# TS1A.net
KiCad netlist of a schematic drawn in Altium Designer
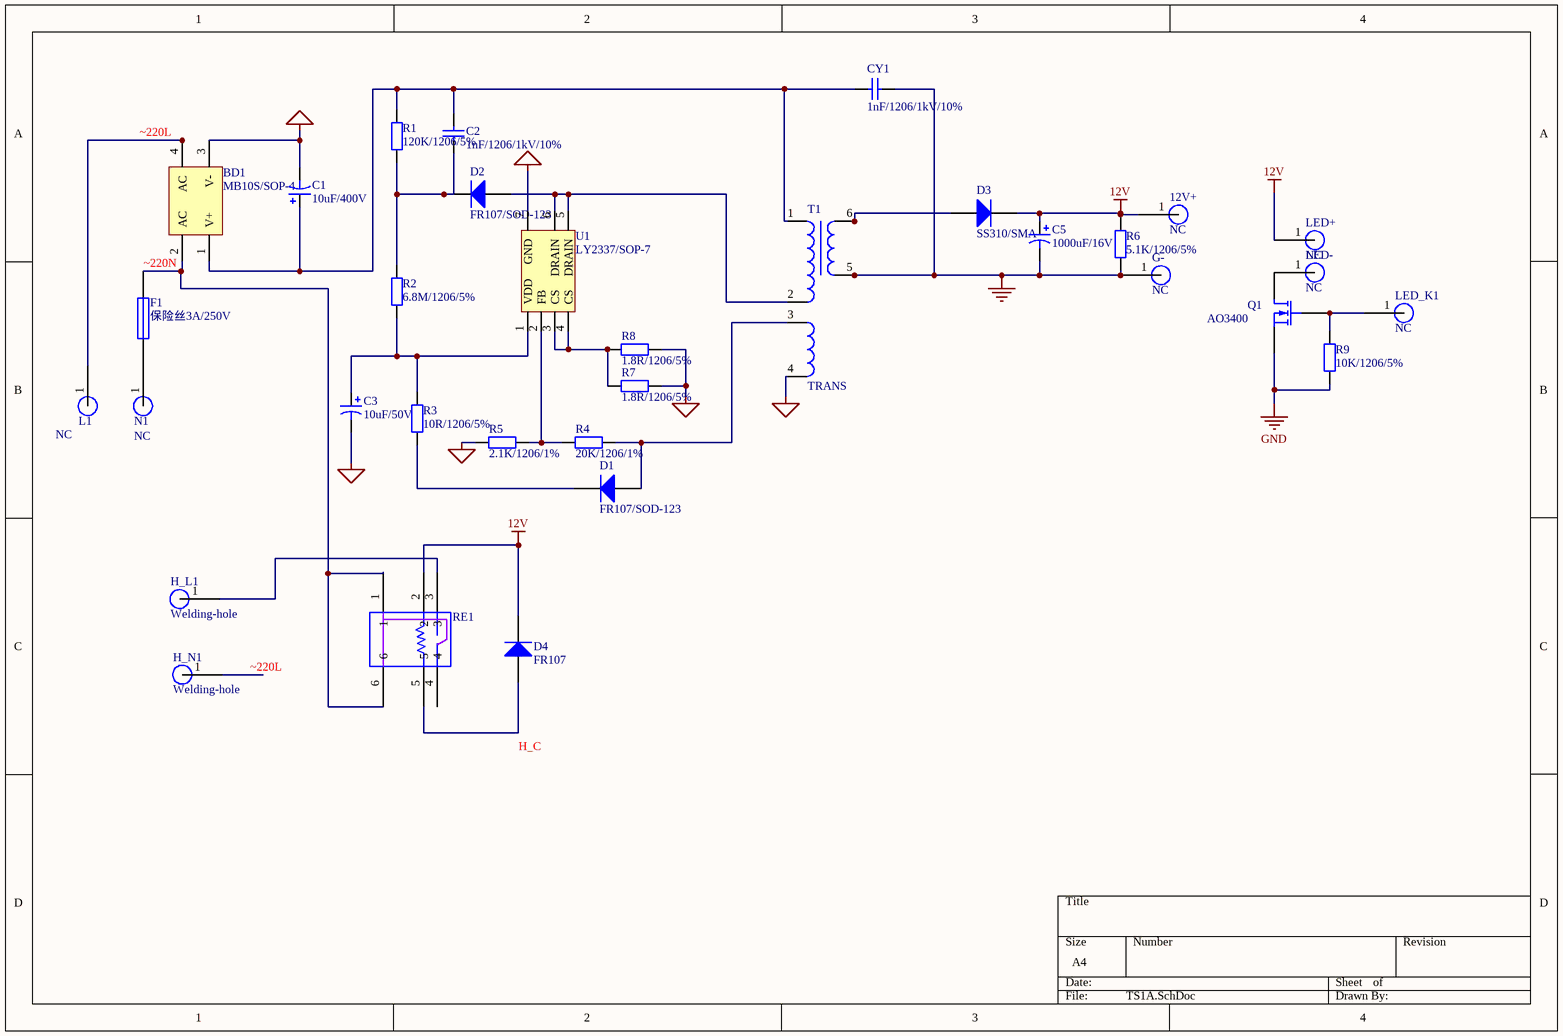
[diagram p0: TS1A.SchDoc]

(export (version "E")
  (design (tool "Eeschema 10.0.6"))
  (components
    (comp (ref "12V+")
      (value "NC")
      (footprint "PAD")
      (description "焊接点")
      (libsource (lib "TS_2A") (part "Welding-hole"))
    )
    (comp (ref "BD1")
      (value "MB10S/SOP-4")
      (footprint "MBL10S")
      (description "整流桥 MB10S/SOP-4")
      (fields (field (name "PUBLISHER") "Altium Limited"))
      (libsource (lib "Miscellaneous Devices") (part "Bridge2"))
    )
    (comp (ref "C1")
      (value "10uF/400V")
      (footprint "400V/10uF 直插电解电容")
      (description "直插电解电容10uF/400V")
      (fields (field (name "PUBLISHER") "Altium Limited"))
      (libsource (lib "Miscellaneous Devices") (part "Cap Pol1"))
    )
    (comp (ref "C2")
      (value "1nF/1206/1kV/10%")
      (footprint "C1206")
      (description "1nF/1206/50V/10%")
      (fields (field (name "PUBLISHER") "Altium Limited"))
      (libsource (lib "Miscellaneous Devices") (part "Cap"))
    )
    (comp (ref "C3")
      (value "10uF/50V")
      (footprint "50V/10uF")
      (description "直插电解电容10uF/50V")
      (fields (field (name "PUBLISHER") "Altium Limited"))
      (libsource (lib "Miscellaneous Devices") (part "Cap Pol1"))
    )
    (comp (ref "C5")
      (value "1000uF/16V")
      (footprint "16V/1000uF")
      (description "直插电解电容1000uF/16V")
      (fields (field (name "PUBLISHER") "Altium Limited"))
      (libsource (lib "Miscellaneous Devices") (part "Cap Pol1"))
    )
    (comp (ref "CY1")
      (value "1nF/1206/1kV/10%")
      (footprint "C1206")
      (description "1nF/1206/50V/10%")
      (fields (field (name "PUBLISHER") "Altium Limited"))
      (libsource (lib "Miscellaneous Devices") (part "Cap"))
    )
    (comp (ref "D1")
      (value "FR107/SOD-123")
      (footprint "SOD123")
      (description "快恢复二极管 FR107 封装SOD-123")
      (fields (field (name "PUBLISHER") "Altium Limited"))
      (libsource (lib "Miscellaneous Devices") (part "Diode"))
    )
    (comp (ref "D2")
      (value "FR107/SOD-123")
      (footprint "SOD123")
      (description "快恢复二极管 FR107 封装SOD-123")
      (fields (field (name "PUBLISHER") "Altium Limited"))
      (libsource (lib "Miscellaneous Devices") (part "Diode"))
    )
    (comp (ref "D3")
      (value "SS310/SMA")
      (footprint "SMA")
      (description "肖特基二极管 SS310/封装 SMA")
      (fields (field (name "PUBLISHER") "Altium Limited"))
      (libsource (lib "Miscellaneous Devices") (part "Diode"))
    )
    (comp (ref "D4")
      (value "FR107")
      (footprint "SOD123")
      (description "Default Diode")
      (fields (field (name "PUBLISHER") "Altium Limited"))
      (libsource (lib "Miscellaneous Devices") (part "Diode"))
    )
    (comp (ref "F1")
      (value "保险丝3A/250V")
      (footprint "FUSE")
      (fields (field (name "PUBLISHER") "Altium Limited"))
      (libsource (lib "Miscellaneous Devices") (part "Fuse 1"))
    )
    (comp (ref "G-")
      (value "NC")
      (footprint "PAD")
      (description "焊接点")
      (libsource (lib "TS_2A") (part "Welding-hole"))
    )
    (comp (ref "H_L1")
      (value "Welding-hole")
      (footprint "PAD")
      (description "焊接点")
      (libsource (lib "TS_2A") (part "Welding-hole"))
    )
    (comp (ref "H_N1")
      (value "Welding-hole")
      (footprint "PAD")
      (description "焊接点")
      (libsource (lib "TS_2A") (part "Welding-hole"))
    )
    (comp (ref "L1")
      (value "NC")
      (footprint "PAD")
      (description "焊接点")
      (libsource (lib "TS_2A") (part "Welding-hole"))
    )
    (comp (ref "LED+")
      (value "NC")
      (footprint "PAD")
      (description "焊接点")
      (libsource (lib "TS_2A") (part "Welding-hole"))
    )
    (comp (ref "LED-")
      (value "NC")
      (footprint "PAD")
      (description "焊接点")
      (libsource (lib "TS_2A") (part "Welding-hole"))
    )
    (comp (ref "LED_K1")
      (value "NC")
      (footprint "PAD")
      (description "焊接点")
      (libsource (lib "TS_2A") (part "Welding-hole"))
    )
    (comp (ref "N1")
      (value "NC")
      (footprint "PAD")
      (description "焊接点")
      (libsource (lib "TS_2A") (part "Welding-hole"))
    )
    (comp (ref "Q1")
      (value "AO3400")
      (footprint "SOT_23_N-MOS")
      (description "N-MOS管 AO3400/SOT23")
      (fields (field (name "PUBLISHER") "Altium Limited"))
      (libsource (lib "Miscellaneous Devices") (part "MOSFET-N"))
    )
    (comp (ref "R1")
      (value "120K/1206/5%")
      (footprint "R1206")
      (description "Resistor 120K/1206/5%")
      (fields (field (name "PUBLISHER") "Altium Limited"))
      (libsource (lib "Miscellaneous Devices") (part "Res2"))
    )
    (comp (ref "R2")
      (value "6.8M/1206/5%")
      (footprint "R1206")
      (description "Resistor 6.8M/1206/5%  6.8兆欧姆")
      (fields (field (name "PUBLISHER") "Altium Limited"))
      (libsource (lib "Miscellaneous Devices") (part "Res2"))
    )
    (comp (ref "R3")
      (value "10R/1206/5%")
      (footprint "R1206")
      (description "Resistor 10R/1206/5%")
      (fields (field (name "PUBLISHER") "Altium Limited"))
      (libsource (lib "") (part "Res2_1"))
    )
    (comp (ref "R4")
      (value "20K/1206/1%")
      (footprint "R1206")
      (description "Resistor 20K/1206/1%")
      (fields (field (name "PUBLISHER") "Altium Limited"))
      (libsource (lib "") (part "Res2_2"))
    )
    (comp (ref "R5")
      (value "2.1K/1206/1%")
      (footprint "R1206")
      (description "Resistor 2.1K/1206/1%")
      (fields (field (name "PUBLISHER") "Altium Limited"))
      (libsource (lib "") (part "Res2_2"))
    )
    (comp (ref "R6")
      (value "5.1K/1206/5%")
      (footprint "R1206")
      (description "Resistor 5.1K/1206/5%")
      (fields (field (name "PUBLISHER") "Altium Limited"))
      (libsource (lib "Miscellaneous Devices") (part "Res2"))
    )
    (comp (ref "R7")
      (value "1.8R/1206/5%")
      (footprint "R1206")
      (description "Resistor 2R/1206/5%")
      (fields (field (name "PUBLISHER") "Altium Limited"))
      (libsource (lib "") (part "Res2_2"))
    )
    (comp (ref "R8")
      (value "1.8R/1206/5%")
      (footprint "R1206")
      (description "Resistor 2R/1206/5%")
      (fields (field (name "PUBLISHER") "Altium Limited"))
      (libsource (lib "") (part "Res2_2"))
    )
    (comp (ref "R9")
      (value "10K/1206/5%")
      (footprint "R1206")
      (description "Resistor 10K/1206/5%")
      (fields (field (name "PUBLISHER") "Altium Limited"))
      (libsource (lib "") (part "Res2_1"))
    )
    (comp (ref "RE1")
      (value "RELAY-BSZ6-SS-112L")
      (footprint "HKE_HRS1_DC12v")
      (description "RELAY-6P")
      (libsource (lib "Schlib1") (part "RELAY-6P"))
    )
    (comp (ref "T1")
      (value "TRANS")
      (footprint "TRANS(EE19)")
      (description "变压器")
      (libsource (lib "Schlib1") (part "TRANS"))
    )
    (comp (ref "U1")
      (value "LY2337/SOP-7")
      (footprint "SOP-7")
      (libsource (lib "Schlib1") (part "Component_1"))
    )
  )
  (nets
    (net (code "2") (name "/~220L") (class "Default")
      (node (ref "BD1") (pin "4") (pinfunction "AC_4") (pintype "passive"))
      (node (ref "H_N1") (pin "1") (pinfunction "1_1") (pintype "passive"))
      (node (ref "L1") (pin "1") (pinfunction "1_1") (pintype "passive"))
    )
    (net (code "3") (name "/~220N") (class "Default")
      (node (ref "BD1") (pin "2") (pinfunction "AC_2") (pintype "passive"))
      (node (ref "F1") (pin "2") (pinfunction "2_2") (pintype "passive"))
      (node (ref "RE1") (pin "1") (pinfunction "1_1") (pintype "passive"))
      (node (ref "RE1") (pin "6") (pinfunction "6_6") (pintype "passive"))
    )
    (net (code "4") (name "12V") (class "Default")
      (node (ref "12V+") (pin "1") (pinfunction "1_1") (pintype "passive"))
      (node (ref "C5") (pin "1") (pinfunction "1_1") (pintype "passive"))
      (node (ref "D3") (pin "2") (pinfunction "K_2") (pintype "passive"))
      (node (ref "D4") (pin "2") (pinfunction "K_2") (pintype "passive"))
      (node (ref "LED+") (pin "1") (pinfunction "1_1") (pintype "passive"))
      (node (ref "R6") (pin "2") (pinfunction "2_2") (pintype "passive"))
      (node (ref "RE1") (pin "2") (pinfunction "2_2") (pintype "passive"))
    )
    (net (code "5") (name "AGND") (class "Default")
      (node (ref "BD1") (pin "3") (pinfunction "V-_3") (pintype "passive"))
      (node (ref "C1") (pin "2") (pinfunction "2_2") (pintype "passive"))
      (node (ref "C3") (pin "2") (pinfunction "2_2") (pintype "passive"))
      (node (ref "R5") (pin "1") (pinfunction "1_1") (pintype "passive"))
      (node (ref "R7") (pin "2") (pinfunction "2_2") (pintype "passive"))
      (node (ref "R8") (pin "2") (pinfunction "2_2") (pintype "passive"))
      (node (ref "T1") (pin "4") (pinfunction "5_4") (pintype "passive"))
      (node (ref "U1") (pin "7") (pinfunction "GND_7") (pintype "passive"))
    )
    (net (code "6") (name "GND") (class "Default")
      (node (ref "C5") (pin "2") (pinfunction "2_2") (pintype "passive"))
      (node (ref "CY1") (pin "2") (pinfunction "2_2") (pintype "passive"))
      (node (ref "G-") (pin "1") (pinfunction "1_1") (pintype "passive"))
      (node (ref "Q1") (pin "3") (pinfunction "S_3") (pintype "passive"))
      (node (ref "R6") (pin "1") (pinfunction "1_1") (pintype "passive"))
      (node (ref "R9") (pin "2") (pinfunction "2_2") (pintype "passive"))
      (node (ref "T1") (pin "5") (pinfunction "5_5") (pintype "passive"))
    )
    (net (code "7") (name "Net-(BD1-V+)") (class "Default")
      (node (ref "BD1") (pin "1") (pinfunction "V+_1") (pintype "passive"))
      (node (ref "C1") (pin "1") (pinfunction "1_1") (pintype "passive"))
      (node (ref "C2") (pin "2") (pinfunction "2_2") (pintype "passive"))
      (node (ref "CY1") (pin "1") (pinfunction "1_1") (pintype "passive"))
      (node (ref "R1") (pin "2") (pinfunction "2_2") (pintype "passive"))
      (node (ref "T1") (pin "1") (pinfunction "1_1") (pintype "passive"))
    )
    (net (code "8") (name "Net-(D1-A)") (class "Default")
      (node (ref "D1") (pin "1") (pinfunction "A_1") (pintype "passive"))
      (node (ref "R4") (pin "2") (pinfunction "2_2") (pintype "passive"))
      (node (ref "T1") (pin "3") (pinfunction "3_3") (pintype "passive"))
    )
    (net (code "9") (name "Net-(D1-K)") (class "Default")
      (node (ref "D1") (pin "2") (pinfunction "K_2") (pintype "passive"))
      (node (ref "R3") (pin "2") (pinfunction "2_2") (pintype "passive"))
    )
    (net (code "10") (name "Net-(D2-A)") (class "Default")
      (node (ref "D2") (pin "1") (pinfunction "A_1") (pintype "passive"))
      (node (ref "T1") (pin "2") (pinfunction "2_2") (pintype "passive"))
      (node (ref "U1") (pin "5") (pinfunction "DRAIN_5") (pintype "passive"))
      (node (ref "U1") (pin "6") (pinfunction "DRAIN_6") (pintype "passive"))
    )
    (net (code "11") (name "Net-(D2-K)") (class "Default")
      (node (ref "C2") (pin "1") (pinfunction "1_1") (pintype "passive"))
      (node (ref "D2") (pin "2") (pinfunction "K_2") (pintype "passive"))
      (node (ref "R1") (pin "1") (pinfunction "1_1") (pintype "passive"))
      (node (ref "R2") (pin "2") (pinfunction "2_2") (pintype "passive"))
    )
    (net (code "12") (name "Net-(D3-A)") (class "Default")
      (node (ref "D3") (pin "1") (pinfunction "A_1") (pintype "passive"))
      (node (ref "T1") (pin "6") (pinfunction "6_6") (pintype "passive"))
    )
    (net (code "13") (name "Net-(D4-A)") (class "Default")
      (node (ref "D4") (pin "1") (pinfunction "A_1") (pintype "passive"))
      (node (ref "RE1") (pin "5") (pinfunction "5_5") (pintype "passive"))
    )
    (net (code "14") (name "Net-(F1-Pad1)") (class "Default")
      (node (ref "F1") (pin "1") (pinfunction "1_1") (pintype "passive"))
      (node (ref "N1") (pin "1") (pinfunction "1_1") (pintype "passive"))
    )
    (net (code "15") (name "Net-(H_L1-Pad1)") (class "Default")
      (node (ref "H_L1") (pin "1") (pinfunction "1_1") (pintype "passive"))
      (node (ref "RE1") (pin "3") (pinfunction "3_3") (pintype "passive"))
    )
    (net (code "16") (name "Net-(Q1-D)") (class "Default")
      (node (ref "LED-") (pin "1") (pinfunction "1_1") (pintype "passive"))
      (node (ref "Q1") (pin "1") (pinfunction "D_1") (pintype "passive"))
    )
    (net (code "17") (name "Net-(Q1-G)") (class "Default")
      (node (ref "LED_K1") (pin "1") (pinfunction "1_1") (pintype "passive"))
      (node (ref "Q1") (pin "2") (pinfunction "G_2") (pintype "passive"))
      (node (ref "R9") (pin "1") (pinfunction "1_1") (pintype "passive"))
    )
    (net (code "18") (name "Net-(R7-Pad1)") (class "Default")
      (node (ref "R7") (pin "1") (pinfunction "1_1") (pintype "passive"))
      (node (ref "R8") (pin "1") (pinfunction "1_1") (pintype "passive"))
      (node (ref "U1") (pin "3") (pinfunction "CS_3") (pintype "passive"))
      (node (ref "U1") (pin "4") (pinfunction "CS_4") (pintype "passive"))
    )
    (net (code "19") (name "Net-(U1-FB)") (class "Default")
      (node (ref "R4") (pin "1") (pinfunction "1_1") (pintype "passive"))
      (node (ref "R5") (pin "2") (pinfunction "2_2") (pintype "passive"))
      (node (ref "U1") (pin "2") (pinfunction "FB_2") (pintype "passive"))
    )
    (net (code "20") (name "Net-(U1-VDD)") (class "Default")
      (node (ref "C3") (pin "1") (pinfunction "1_1") (pintype "passive"))
      (node (ref "R2") (pin "1") (pinfunction "1_1") (pintype "passive"))
      (node (ref "R3") (pin "1") (pinfunction "1_1") (pintype "passive"))
      (node (ref "U1") (pin "1") (pinfunction "VDD_1") (pintype "passive"))
    )
    (net (code "21") (name "unconnected-(RE1-Pad4)") (class "Default")
      (node (ref "RE1") (pin "4") (pinfunction "4_4") (pintype "passive"))
    )
  )
)
